# Page05_DDR4L_eMMC.net
KiCad netlist of a schematic drawn in Altium Designer
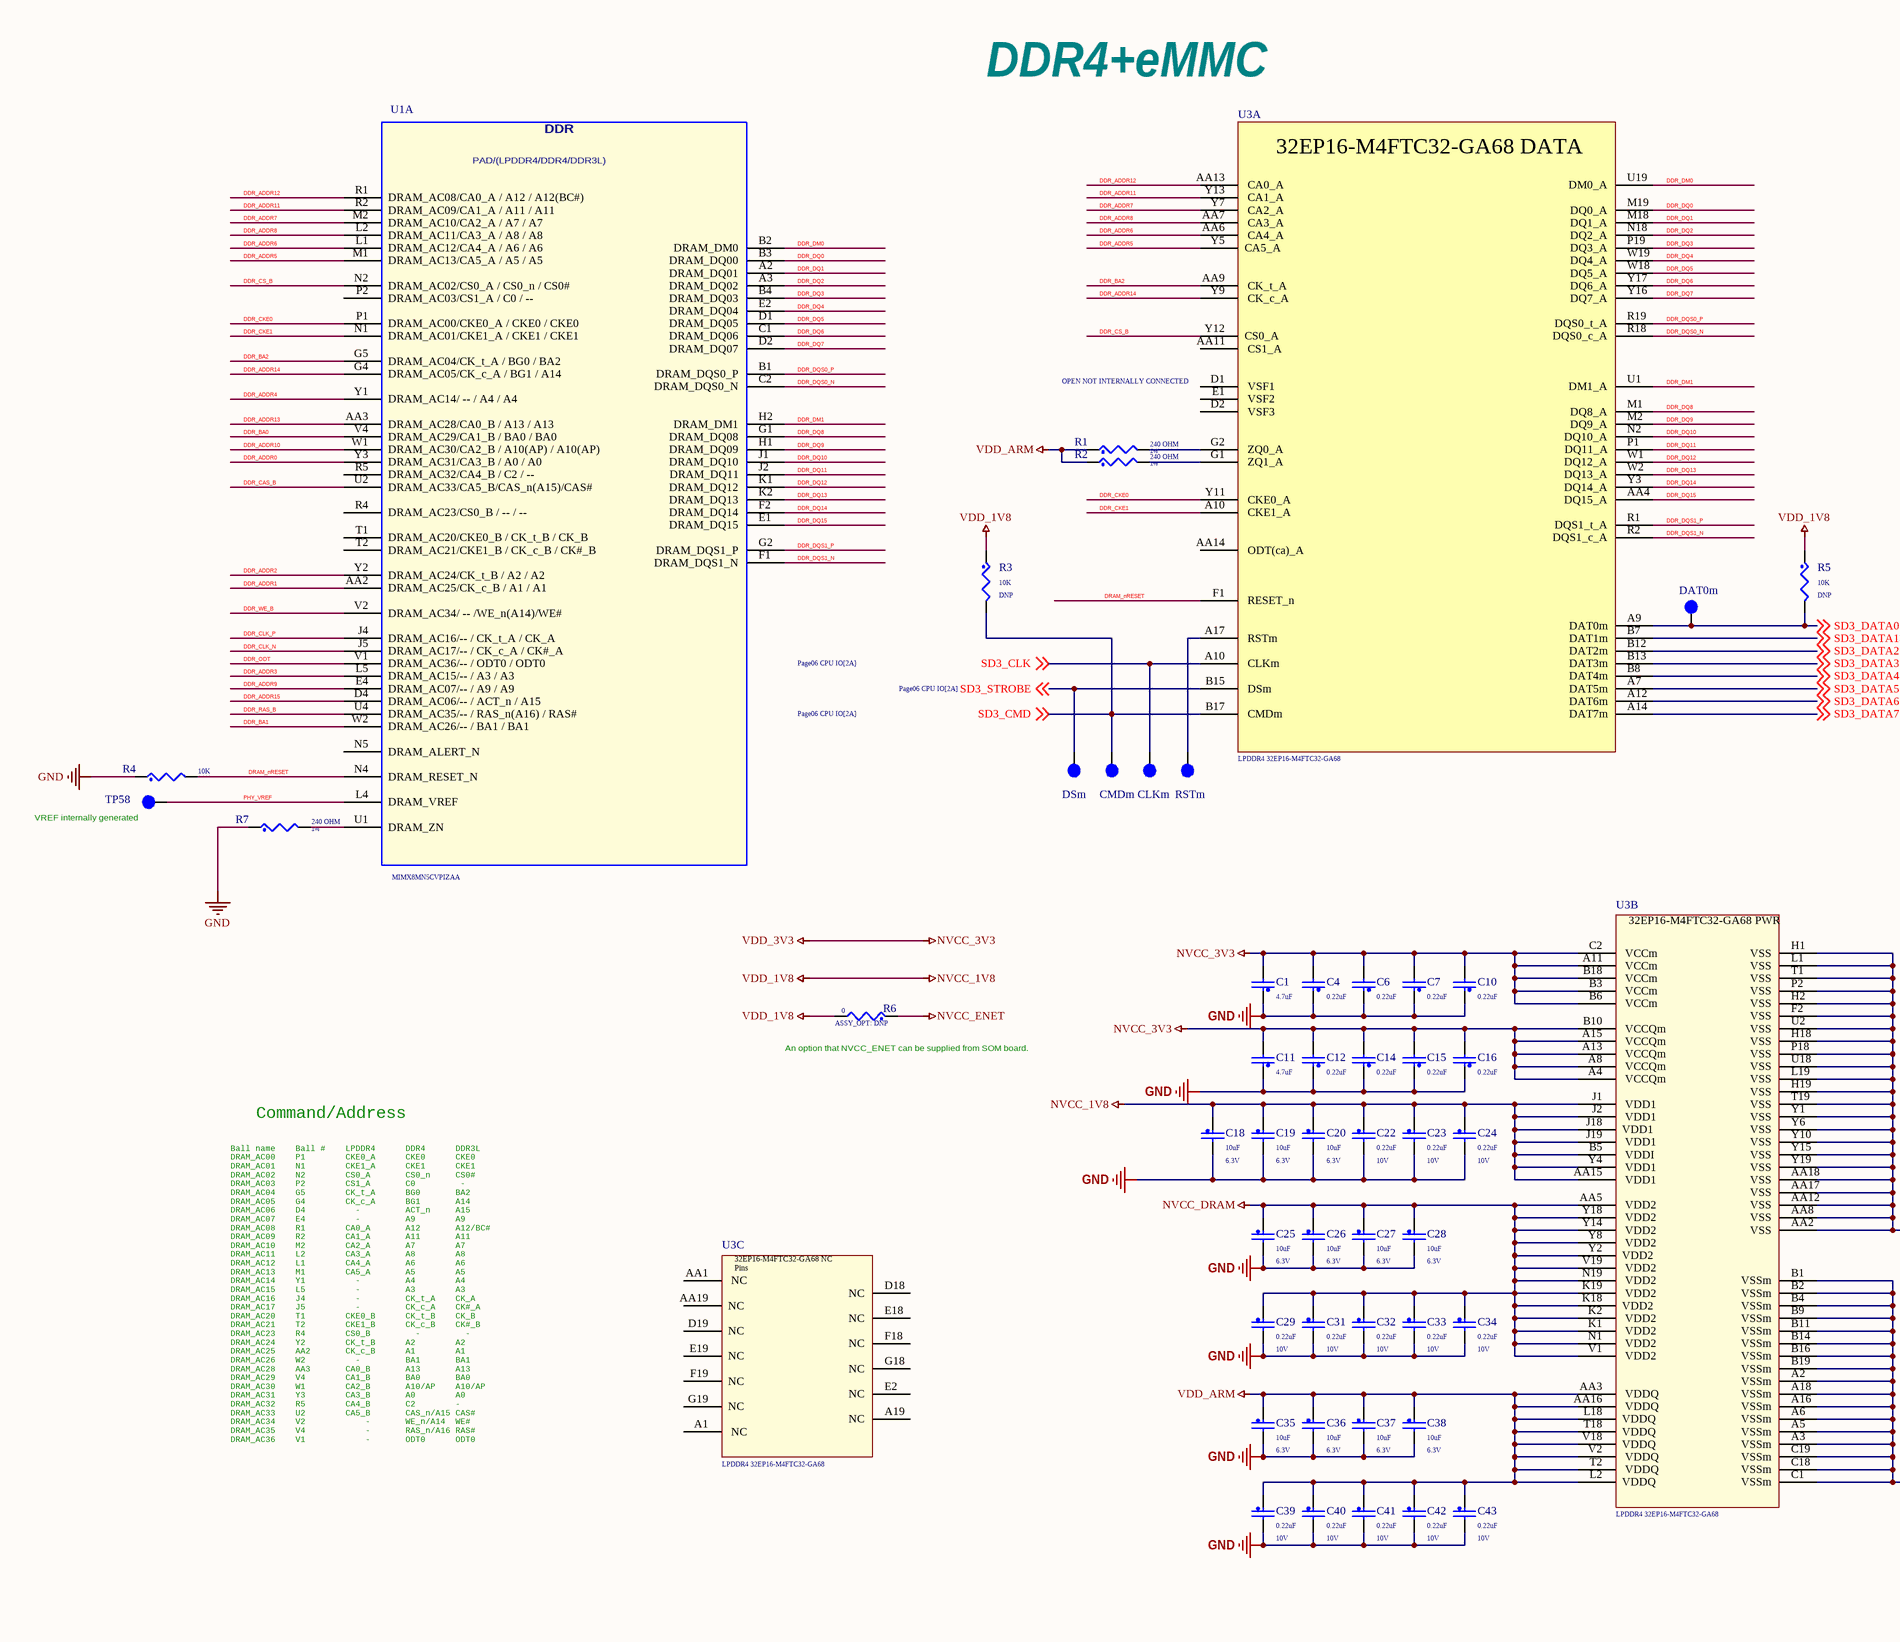
[diagram p0: Page05 DDR4L+eMMC.SchDoc, left]
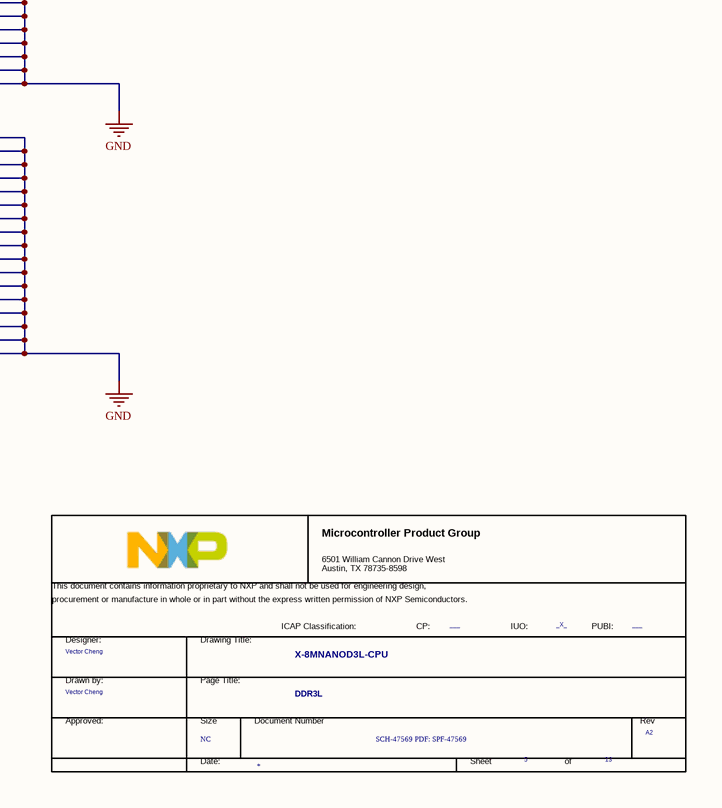
[diagram p1: Page05 DDR4L+eMMC.SchDoc, right]

(export (version "E")
  (design (tool "Eeschema 10.0.6"))
  (components
    (comp (ref "C1") (value "4.7uF") (footprint "0402_CC - C") (libsource (lib "AA_iMX8_M_") (part "CAP_NP")))
    (comp (ref "C4")
      (value "0.22uF")
      (footprint "0201_CC - C")
      (libsource (lib "AA_iMX8_M_") (part "CAP_NP"))
    )
    (comp (ref "C6")
      (value "0.22uF")
      (footprint "0201_CC - C")
      (libsource (lib "AA_iMX8_M_") (part "CAP_NP"))
    )
    (comp (ref "C7")
      (value "0.22uF")
      (footprint "0201_CC - C")
      (libsource (lib "AA_iMX8_M_") (part "CAP_NP"))
    )
    (comp (ref "C10")
      (value "0.22uF")
      (footprint "0201_CC - C")
      (libsource (lib "AA_iMX8_M_") (part "CAP_NP"))
    )
    (comp (ref "C11")
      (value "4.7uF")
      (footprint "0402_CC - C")
      (libsource (lib "AA_iMX8_M_") (part "CAP_NP"))
    )
    (comp (ref "C12")
      (value "0.22uF")
      (footprint "0201_CC - C")
      (libsource (lib "AA_iMX8_M_") (part "CAP_NP"))
    )
    (comp (ref "C14")
      (value "0.22uF")
      (footprint "0201_CC - C")
      (libsource (lib "AA_iMX8_M_") (part "CAP_NP"))
    )
    (comp (ref "C15")
      (value "0.22uF")
      (footprint "0201_CC - C")
      (libsource (lib "AA_iMX8_M_") (part "CAP_NP"))
    )
    (comp (ref "C16")
      (value "0.22uF")
      (footprint "0201_CC - C")
      (libsource (lib "AA_iMX8_M_") (part "CAP_NP"))
    )
    (comp (ref "C18")
      (value "10uF")
      (footprint "0402_CC - C")
      (fields (field (name "VOLTAGE") "6.3V"))
      (libsource (lib "AA_iMX8_M_") (part "CAP_NP"))
    )
    (comp (ref "C19")
      (value "10uF")
      (footprint "0402_CC - C")
      (fields (field (name "VOLTAGE") "6.3V"))
      (libsource (lib "AA_iMX8_M_") (part "CAP_NP"))
    )
    (comp (ref "C20")
      (value "10uF")
      (footprint "0402_CC - C")
      (fields (field (name "VOLTAGE") "6.3V"))
      (libsource (lib "AA_iMX8_M_") (part "CAP_NP"))
    )
    (comp (ref "C22")
      (value "0.22uF")
      (footprint "0201_CC - C")
      (fields (field (name "VOLTAGE") "10V"))
      (libsource (lib "AA_iMX8_M_") (part "CAP_NP"))
    )
    (comp (ref "C23")
      (value "0.22uF")
      (footprint "0201_CC - C")
      (fields (field (name "VOLTAGE") "10V"))
      (libsource (lib "AA_iMX8_M_") (part "CAP_NP"))
    )
    (comp (ref "C24")
      (value "0.22uF")
      (footprint "0201_CC - C")
      (fields (field (name "VOLTAGE") "10V"))
      (libsource (lib "AA_iMX8_M_") (part "CAP_NP"))
    )
    (comp (ref "C25")
      (value "10uF")
      (footprint "0402_CC - C")
      (fields (field (name "VOLTAGE") "6.3V"))
      (libsource (lib "AA_iMX8_M_") (part "CAP_NP"))
    )
    (comp (ref "C26")
      (value "10uF")
      (footprint "0402_CC - C")
      (fields (field (name "VOLTAGE") "6.3V"))
      (libsource (lib "AA_iMX8_M_") (part "CAP_NP"))
    )
    (comp (ref "C27")
      (value "10uF")
      (footprint "0402_CC - C")
      (fields (field (name "VOLTAGE") "6.3V"))
      (libsource (lib "AA_iMX8_M_") (part "CAP_NP"))
    )
    (comp (ref "C28")
      (value "10uF")
      (footprint "0402_CC - C")
      (fields (field (name "VOLTAGE") "6.3V"))
      (libsource (lib "AA_iMX8_M_") (part "CAP_NP"))
    )
    (comp (ref "C29")
      (value "0.22uF")
      (footprint "0201_CC - C")
      (fields (field (name "VOLTAGE") "10V"))
      (libsource (lib "AA_iMX8_M_") (part "CAP_NP"))
    )
    (comp (ref "C31")
      (value "0.22uF")
      (footprint "0201_CC - C")
      (fields (field (name "VOLTAGE") "10V"))
      (libsource (lib "AA_iMX8_M_") (part "CAP_NP"))
    )
    (comp (ref "C32")
      (value "0.22uF")
      (footprint "0201_CC - C")
      (fields (field (name "VOLTAGE") "10V"))
      (libsource (lib "AA_iMX8_M_") (part "CAP_NP"))
    )
    (comp (ref "C33")
      (value "0.22uF")
      (footprint "0201_CC - C")
      (fields (field (name "VOLTAGE") "10V"))
      (libsource (lib "AA_iMX8_M_") (part "CAP_NP"))
    )
    (comp (ref "C34")
      (value "0.22uF")
      (footprint "0201_CC - C")
      (fields (field (name "VOLTAGE") "10V"))
      (libsource (lib "AA_iMX8_M_") (part "CAP_NP"))
    )
    (comp (ref "C35")
      (value "10uF")
      (footprint "0402_CC - C")
      (fields (field (name "VOLTAGE") "6.3V"))
      (libsource (lib "AA_iMX8_M_") (part "CAP_NP"))
    )
    (comp (ref "C36")
      (value "10uF")
      (footprint "0402_CC - C")
      (fields (field (name "VOLTAGE") "6.3V"))
      (libsource (lib "AA_iMX8_M_") (part "CAP_NP"))
    )
    (comp (ref "C37")
      (value "10uF")
      (footprint "0402_CC - C")
      (fields (field (name "VOLTAGE") "6.3V"))
      (libsource (lib "AA_iMX8_M_") (part "CAP_NP"))
    )
    (comp (ref "C38")
      (value "10uF")
      (footprint "0402_CC - C")
      (fields (field (name "VOLTAGE") "6.3V"))
      (libsource (lib "AA_iMX8_M_") (part "CAP_NP"))
    )
    (comp (ref "C39")
      (value "0.22uF")
      (footprint "0201_CC - C")
      (fields (field (name "VOLTAGE") "10V"))
      (libsource (lib "AA_iMX8_M_") (part "CAP_NP"))
    )
    (comp (ref "C40")
      (value "0.22uF")
      (footprint "0201_CC - C")
      (fields (field (name "VOLTAGE") "10V"))
      (libsource (lib "AA_iMX8_M_") (part "CAP_NP"))
    )
    (comp (ref "C41")
      (value "0.22uF")
      (footprint "0201_CC - C")
      (fields (field (name "VOLTAGE") "10V"))
      (libsource (lib "AA_iMX8_M_") (part "CAP_NP"))
    )
    (comp (ref "C42")
      (value "0.22uF")
      (footprint "0201_CC - C")
      (fields (field (name "VOLTAGE") "10V"))
      (libsource (lib "AA_iMX8_M_") (part "CAP_NP"))
    )
    (comp (ref "C43")
      (value "0.22uF")
      (footprint "0201_CC - C")
      (fields (field (name "VOLTAGE") "10V"))
      (libsource (lib "AA_iMX8_M_") (part "CAP_NP"))
    )
    (comp (ref "CLKm")
      (value "tpad_020")
      (footprint "Test Pin")
      (description "TEST POINT PAD 0.5MM DIA SMT, NO PART TO ORDER")
      (libsource (lib "*") (part "TESTLOOP"))
    )
    (comp (ref "CMDm")
      (value "TPAD_015")
      (footprint "Test Pin")
      (description "TEST POINT PAD 15MIL DIA SMT, NO PART TO ORDER")
      (libsource (lib "*") (part "TESTLOOP"))
    )
    (comp (ref "DAT0m")
      (value "tpad_020")
      (footprint "Test Pin")
      (description "TEST POINT PAD 0.5MM DIA SMT, NO PART TO ORDER")
      (libsource (lib "*") (part "TESTLOOP"))
    )
    (comp (ref "DSm")
      (value "TPAD_015")
      (footprint "Test Pin")
      (description "TEST POINT PAD 15MIL DIA SMT, NO PART TO ORDER")
      (libsource (lib "*") (part "TESTLOOP"))
    )
    (comp (ref "R1")
      (value "240 OHM")
      (footprint "0201_RES")
      (description "RES MF 240 OHM 1/20W 1% 0201")
      (fields (field (name "VOLTAGE") "25V") (field (name "TOLERANCE") "1%"))
      (libsource (lib "*") (part "RES"))
    )
    (comp (ref "R2")
      (value "240 OHM")
      (footprint "0201_RES")
      (description "RES MF 240 OHM 1/20W 1% 0201")
      (fields (field (name "VOLTAGE") "25V") (field (name "TOLERANCE") "1%"))
      (libsource (lib "*") (part "RES"))
    )
    (comp (ref "R3")
      (value "10K")
      (footprint "0201_RES")
      (description "RES MF 10K 1/20W 5% 0201")
      (fields (field (name "ASSY_OPT") "DNP") (field (name "TOLERANCE") "5%"))
      (libsource (lib "*") (part "RES"))
    )
    (comp (ref "R4")
      (value "10K")
      (footprint "0201_RES")
      (description "RES MF 10K 1/20W 5% 0201")
      (fields (field (name "TOLERANCE") "5%"))
      (libsource (lib "*") (part "RES"))
    )
    (comp (ref "R5")
      (value "10K")
      (footprint "0201_RES")
      (description "RES MF 10K 1/20W 5% 0201")
      (fields (field (name "ASSY_OPT") "DNP") (field (name "TOLERANCE") "5%"))
      (libsource (lib "*") (part "RES"))
    )
    (comp (ref "R6")
      (value "0")
      (footprint "0402_CC_RES")
      (description "RES MF ZERO OHM 1/16W 5% 0402")
      (fields
        (field (name "ASSY_OPT") "DNP")
        (field (name "TOLERANCE") "5%")
        (field (name "VOLTAGE") "1/16W")
      )
      (libsource (lib "*") (part "RES"))
    )
    (comp (ref "R7")
      (value "240 OHM")
      (footprint "0201_RES")
      (description "RES MF 240 OHM 1/20W 1% 0201")
      (fields (field (name "VOLTAGE") "25V") (field (name "TOLERANCE") "1%"))
      (libsource (lib "*") (part "RES"))
    )
    (comp (ref "RSTm")
      (value "tpad_020")
      (footprint "Test Pin")
      (description "TEST POINT PAD 0.5MM DIA SMT, NO PART TO ORDER")
      (libsource (lib "*") (part "TESTLOOP"))
    )
    (comp (ref "TP58")
      (value "tpad_020")
      (footprint "Test Pin")
      (description "TEST POINT PAD 0.5MM DIA SMT, NO PART TO ORDER")
      (libsource (lib "*") (part "TESTLOOP"))
    )
    (comp (ref "U1")
      (value "MIMX8MN5CVPIZAA")
      (footprint "BGA306C50P21X21_1100X1100X101")
      (description "IC CPU QUAD CORTEX A53+M7 1.4GHZ -- BGA306")
      (libsource (lib "*") (part "MIMX8MN"))
    )
    (comp (ref "U3")
      (value "LPDDR4 32EP16-M4FTC32-GA68")
      (footprint "FBGA144C40P19X21_800X950X80")
      (libsource (lib "") (part "LPDDR4 32EP16-M4FTC32-GA68_1"))
    )
  )
  (nets
    (net (code "1") (name "/DDR_ADDR0") (class "Default")
      (node (ref "U1") (pin "Y3") (pinfunction "DRAM_AC31/CA3_B_/_A0_/_A0_Y3") (pintype "passive"))
    )
    (net (code "2") (name "/DDR_ADDR1") (class "Default")
      (node (ref "U1") (pin "AA2") (pinfunction "DRAM_AC25/CK_c_B_/_A1_/_A1_AA2") (pintype "passive"))
    )
    (net (code "3") (name "/DDR_ADDR2") (class "Default")
      (node (ref "U1") (pin "Y2") (pinfunction "DRAM_AC24/CK_t_B_/_A2_/_A2_Y2") (pintype "passive"))
    )
    (net (code "4") (name "/DDR_ADDR3") (class "Default")
      (node (ref "U1") (pin "L5") (pinfunction "DRAM_AC15/--_/_A3_/_A3_L5") (pintype "passive"))
    )
    (net (code "5") (name "/DDR_ADDR4") (class "Default")
      (node (ref "U1") (pin "Y1") (pinfunction "DRAM_AC14/_--_/_A4_/_A4_Y1") (pintype "passive"))
    )
    (net (code "6") (name "/DDR_ADDR5") (class "Default")
      (node (ref "U1") (pin "M1") (pinfunction "DRAM_AC13/CA5_A_/_A5_/_A5_M1") (pintype "passive"))
      (node (ref "U3") (pin "Y5") (pinfunction "CA5_A_Y5") (pintype "passive"))
    )
    (net (code "7") (name "/DDR_ADDR6") (class "Default")
      (node (ref "U1") (pin "L1") (pinfunction "DRAM_AC12/CA4_A_/_A6_/_A6_L1") (pintype "passive"))
      (node (ref "U3") (pin "AA6") (pinfunction "_CA4_A_AA6") (pintype "passive"))
    )
    (net (code "8") (name "/DDR_ADDR7") (class "Default")
      (node (ref "U1") (pin "M2") (pinfunction "DRAM_AC10/CA2_A_/_A7_/_A7_M2") (pintype "passive"))
      (node (ref "U3") (pin "Y7") (pinfunction "_CA2_A_Y7") (pintype "passive"))
    )
    (net (code "9") (name "/DDR_ADDR8") (class "Default")
      (node (ref "U1") (pin "L2") (pinfunction "DRAM_AC11/CA3_A_/_A8_/_A8_L2") (pintype "passive"))
      (node (ref "U3") (pin "AA7") (pinfunction "_CA3_A_AA7") (pintype "passive"))
    )
    (net (code "10") (name "/DDR_ADDR9") (class "Default")
      (node (ref "U1") (pin "E4") (pinfunction "DRAM_AC07/--_/_A9_/_A9_E4") (pintype "passive"))
    )
    (net (code "11") (name "/DDR_ADDR10") (class "Default")
      (node (ref "U1") (pin "W1") (pinfunction "DRAM_AC30/CA2_B_/_A10(AP)_/_A10(AP)_W1") (pintype "passive"))
    )
    (net (code "12") (name "/DDR_ADDR11") (class "Default")
      (node (ref "U1") (pin "R2") (pinfunction "DRAM_AC09/CA1_A_/_A11_/_A11_R2") (pintype "passive"))
      (node (ref "U3") (pin "Y13") (pinfunction "_CA1_A_Y13") (pintype "passive"))
    )
    (net (code "13") (name "/DDR_ADDR12") (class "Default")
      (node (ref "U1") (pin "R1") (pinfunction "DRAM_AC08/CA0_A_/_A12_/_A12(BC#)_R1") (pintype "passive"))
      (node (ref "U3") (pin "AA13") (pinfunction "_CA0_A_AA13") (pintype "passive"))
    )
    (net (code "14") (name "/DDR_ADDR13") (class "Default")
      (node (ref "U1") (pin "AA3") (pinfunction "DRAM_AC28/CA0_B_/_A13_/_A13_AA3") (pintype "passive"))
    )
    (net (code "15") (name "/DDR_ADDR14") (class "Default")
      (node (ref "U1") (pin "G4") (pinfunction "DRAM_AC05/CK_c_A_/_BG1_/_A14_G4") (pintype "passive"))
      (node (ref "U3") (pin "Y9") (pinfunction "_CK_c_A_Y9") (pintype "passive"))
    )
    (net (code "16") (name "/DDR_ADDR15") (class "Default")
      (node (ref "U1") (pin "D4") (pinfunction "DRAM_AC06/--_/_ACT_n_/_A15_D4") (pintype "passive"))
    )
    (net (code "17") (name "/DDR_BA0") (class "Default")
      (node (ref "U1") (pin "V4") (pinfunction "DRAM_AC29/CA1_B_/_BA0_/_BA0_V4") (pintype "passive"))
    )
    (net (code "18") (name "/DDR_BA1") (class "Default")
      (node (ref "U1") (pin "W2") (pinfunction "DRAM_AC26/--_/_BA1_/_BA1_W2") (pintype "passive"))
    )
    (net (code "19") (name "/DDR_BA2") (class "Default")
      (node (ref "U1") (pin "G5") (pinfunction "DRAM_AC04/CK_t_A_/_BG0_/_BA2_G5") (pintype "passive"))
      (node (ref "U3") (pin "AA9") (pinfunction "_CK_t_A_AA9") (pintype "passive"))
    )
    (net (code "20") (name "/DDR_CAS_B") (class "Default")
      (node (ref "U1") (pin "U2") (pinfunction "DRAM_AC33/CA5_B/CAS_n(A15)/CAS#_U2") (pintype "passive"))
    )
    (net (code "21") (name "/DDR_CKE0") (class "Default")
      (node (ref "U1") (pin "P1") (pinfunction "DRAM_AC00/CKE0_A_/_CKE0_/_CKE0_P1") (pintype "passive"))
      (node (ref "U3") (pin "Y11") (pinfunction "_CKE0_A_Y11") (pintype "passive"))
    )
    (net (code "22") (name "/DDR_CKE1") (class "Default")
      (node (ref "U1") (pin "N1") (pinfunction "DRAM_AC01/CKE1_A_/_CKE1_/_CKE1_N1") (pintype "passive"))
      (node (ref "U3") (pin "A10") (pinfunction "_CKE1_A_A10") (pintype "passive"))
    )
    (net (code "23") (name "/DDR_CLK_N") (class "Default")
      (node (ref "U1") (pin "J5") (pinfunction "DRAM_AC17/--_/_CK_c_A_/_CK#_A_J5") (pintype "passive"))
    )
    (net (code "24") (name "/DDR_CLK_P") (class "Default")
      (node (ref "U1") (pin "J4") (pinfunction "DRAM_AC16/--_/_CK_t_A_/_CK_A_J4") (pintype "passive"))
    )
    (net (code "25") (name "/DDR_CS_B") (class "Default")
      (node (ref "U1") (pin "N2") (pinfunction "DRAM_AC02/CS0_A_/_CS0_n_/_CS0#_N2") (pintype "passive"))
      (node (ref "U3") (pin "Y12") (pinfunction "CS0_A_Y12") (pintype "passive"))
    )
    (net (code "26") (name "/DDR_DM0") (class "Default")
      (node (ref "U1") (pin "B2") (pinfunction "DRAM_DM0_B2") (pintype "passive"))
      (node (ref "U3") (pin "U19") (pinfunction "_DM0_A_U19") (pintype "passive"))
    )
    (net (code "27") (name "/DDR_DM1") (class "Default")
      (node (ref "U1") (pin "H2") (pinfunction "DRAM_DM1_H2") (pintype "passive"))
      (node (ref "U3") (pin "U1") (pinfunction "_DM1_A_U1") (pintype "passive"))
    )
    (net (code "28") (name "/DDR_DQ0") (class "Default")
      (node (ref "U1") (pin "B3") (pinfunction "DRAM_DQ00_B3") (pintype "passive"))
      (node (ref "U3") (pin "M19") (pinfunction "_DQ0_A_M19") (pintype "passive"))
    )
    (net (code "29") (name "/DDR_DQ1") (class "Default")
      (node (ref "U1") (pin "A2") (pinfunction "DRAM_DQ01_A2") (pintype "passive"))
      (node (ref "U3") (pin "M18") (pinfunction "DQ1_A_M18") (pintype "passive"))
    )
    (net (code "30") (name "/DDR_DQ2") (class "Default")
      (node (ref "U1") (pin "A3") (pinfunction "DRAM_DQ02_A3") (pintype "passive"))
      (node (ref "U3") (pin "N18") (pinfunction "DQ2_A_N18") (pintype "passive"))
    )
    (net (code "31") (name "/DDR_DQ3") (class "Default")
      (node (ref "U1") (pin "B4") (pinfunction "DRAM_DQ03_B4") (pintype "passive"))
      (node (ref "U3") (pin "P19") (pinfunction "DQ3_A_P19") (pintype "passive"))
    )
    (net (code "32") (name "/DDR_DQ4") (class "Default")
      (node (ref "U1") (pin "E2") (pinfunction "DRAM_DQ04_E2") (pintype "passive"))
      (node (ref "U3") (pin "W19") (pinfunction "_DQ4_A_W19") (pintype "passive"))
    )
    (net (code "33") (name "/DDR_DQ5") (class "Default")
      (node (ref "U1") (pin "D1") (pinfunction "DRAM_DQ05_D1") (pintype "passive"))
      (node (ref "U3") (pin "W18") (pinfunction "DQ5_A_W18") (pintype "passive"))
    )
    (net (code "34") (name "/DDR_DQ6") (class "Default")
      (node (ref "U1") (pin "C1") (pinfunction "DRAM_DQ06_C1") (pintype "passive"))
      (node (ref "U3") (pin "Y17") (pinfunction "_DQ6_A_Y17") (pintype "passive"))
    )
    (net (code "35") (name "/DDR_DQ7") (class "Default")
      (node (ref "U1") (pin "D2") (pinfunction "DRAM_DQ07_D2") (pintype "passive"))
      (node (ref "U3") (pin "Y16") (pinfunction "_DQ7_A_Y16") (pintype "passive"))
    )
    (net (code "36") (name "/DDR_DQ8") (class "Default")
      (node (ref "U1") (pin "G1") (pinfunction "DRAM_DQ08_G1") (pintype "passive"))
      (node (ref "U3") (pin "M1") (pinfunction "_DQ8_A_M1") (pintype "passive"))
    )
    (net (code "37") (name "/DDR_DQ9") (class "Default")
      (node (ref "U1") (pin "H1") (pinfunction "DRAM_DQ09_H1") (pintype "passive"))
      (node (ref "U3") (pin "M2") (pinfunction "_DQ9_A_M2") (pintype "passive"))
    )
    (net (code "38") (name "/DDR_DQ10") (class "Default")
      (node (ref "U1") (pin "J1") (pinfunction "DRAM_DQ10_J1") (pintype "passive"))
      (node (ref "U3") (pin "N2") (pinfunction "_DQ10_A_N2") (pintype "passive"))
    )
    (net (code "39") (name "/DDR_DQ11") (class "Default")
      (node (ref "U1") (pin "J2") (pinfunction "DRAM_DQ11_J2") (pintype "passive"))
      (node (ref "U3") (pin "P1") (pinfunction "_DQ11_A_P1") (pintype "passive"))
    )
    (net (code "40") (name "/DDR_DQ12") (class "Default")
      (node (ref "U1") (pin "K1") (pinfunction "DRAM_DQ12_K1") (pintype "passive"))
      (node (ref "U3") (pin "W1") (pinfunction "_DQ12_A_W1") (pintype "passive"))
    )
    (net (code "41") (name "/DDR_DQ13") (class "Default")
      (node (ref "U1") (pin "K2") (pinfunction "DRAM_DQ13_K2") (pintype "passive"))
      (node (ref "U3") (pin "W2") (pinfunction "_DQ13_A_W2") (pintype "passive"))
    )
    (net (code "42") (name "/DDR_DQ14") (class "Default")
      (node (ref "U1") (pin "F2") (pinfunction "DRAM_DQ14_F2") (pintype "passive"))
      (node (ref "U3") (pin "Y3") (pinfunction "_DQ14_A_Y3") (pintype "passive"))
    )
    (net (code "43") (name "/DDR_DQ15") (class "Default")
      (node (ref "U1") (pin "E1") (pinfunction "DRAM_DQ15_E1") (pintype "passive"))
      (node (ref "U3") (pin "AA4") (pinfunction "_DQ15_A_AA4") (pintype "passive"))
    )
    (net (code "44") (name "/DDR_DQS0_N") (class "Default")
      (node (ref "U1") (pin "C2") (pinfunction "DRAM_DQS0_N_C2") (pintype "passive"))
      (node (ref "U3") (pin "R18") (pinfunction "DQS0_c_A_R18") (pintype "passive"))
    )
    (net (code "45") (name "/DDR_DQS0_P") (class "Default")
      (node (ref "U1") (pin "B1") (pinfunction "DRAM_DQS0_P_B1") (pintype "passive"))
      (node (ref "U3") (pin "R19") (pinfunction "_DQS0_t_A_R19") (pintype "passive"))
    )
    (net (code "46") (name "/DDR_DQS1_N") (class "Default")
      (node (ref "U1") (pin "F1") (pinfunction "DRAM_DQS1_N_F1") (pintype "passive"))
      (node (ref "U3") (pin "R2") (pinfunction "_DQS1_c_A_R2") (pintype "passive"))
    )
    (net (code "47") (name "/DDR_DQS1_P") (class "Default")
      (node (ref "U1") (pin "G2") (pinfunction "DRAM_DQS1_P_G2") (pintype "passive"))
      (node (ref "U3") (pin "R1") (pinfunction "_DQS1_t_A_R1") (pintype "passive"))
    )
    (net (code "48") (name "/DDR_ODT") (class "Default")
      (node (ref "U1") (pin "V1") (pinfunction "DRAM_AC36/--_/_ODT0_/_ODT0_V1") (pintype "passive"))
    )
    (net (code "49") (name "/DDR_RAS_B") (class "Default")
      (node (ref "U1") (pin "U4") (pinfunction "DRAM_AC35/--_/_RAS_n(A16)_/_RAS#_U4") (pintype "passive"))
    )
    (net (code "50") (name "/DDR_WE_B") (class "Default")
      (node (ref "U1") (pin "V2") (pinfunction "DRAM_AC34/_--_/WE_n(A14)/WE#_V2") (pintype "passive"))
    )
    (net (code "51") (name "/DRAM_nRESET") (class "Default")
      (node (ref "R4") (pin "2") (pinfunction "2_2") (pintype "passive"))
      (node (ref "U1") (pin "N4") (pinfunction "DRAM_RESET_N_N4") (pintype "passive"))
      (node (ref "U3") (pin "F1") (pinfunction "_RESET_n_F1") (pintype "passive"))
    )
    (net (code "52") (name "/PHY_VREF") (class "Default")
      (node (ref "TP58") (pin "1") (pinfunction "Pin1_1") (pintype "passive"))
      (node (ref "U1") (pin "L4") (pinfunction "DRAM_VREF_L4") (pintype "passive"))
    )
    (net (code "53") (name "GND") (class "Default")
      (node (ref "C1") (pin "1") (pinfunction "1_1") (pintype "passive"))
      (node (ref "C10") (pin "1") (pinfunction "1_1") (pintype "passive"))
      (node (ref "C11") (pin "1") (pinfunction "1_1") (pintype "passive"))
      (node (ref "C12") (pin "1") (pinfunction "1_1") (pintype "passive"))
      (node (ref "C14") (pin "1") (pinfunction "1_1") (pintype "passive"))
      (node (ref "C15") (pin "1") (pinfunction "1_1") (pintype "passive"))
      (node (ref "C16") (pin "1") (pinfunction "1_1") (pintype "passive"))
      (node (ref "C18") (pin "2") (pinfunction "2_2") (pintype "passive"))
      (node (ref "C19") (pin "2") (pinfunction "2_2") (pintype "passive"))
      (node (ref "C20") (pin "2") (pinfunction "2_2") (pintype "passive"))
      (node (ref "C22") (pin "2") (pinfunction "2_2") (pintype "passive"))
      (node (ref "C23") (pin "2") (pinfunction "2_2") (pintype "passive"))
      (node (ref "C24") (pin "2") (pinfunction "2_2") (pintype "passive"))
      (node (ref "C25") (pin "2") (pinfunction "2_2") (pintype "passive"))
      (node (ref "C26") (pin "2") (pinfunction "2_2") (pintype "passive"))
      (node (ref "C27") (pin "2") (pinfunction "2_2") (pintype "passive"))
      (node (ref "C28") (pin "2") (pinfunction "2_2") (pintype "passive"))
      (node (ref "C29") (pin "2") (pinfunction "2_2") (pintype "passive"))
      (node (ref "C31") (pin "2") (pinfunction "2_2") (pintype "passive"))
      (node (ref "C32") (pin "2") (pinfunction "2_2") (pintype "passive"))
      (node (ref "C33") (pin "2") (pinfunction "2_2") (pintype "passive"))
      (node (ref "C34") (pin "2") (pinfunction "2_2") (pintype "passive"))
      (node (ref "C35") (pin "2") (pinfunction "2_2") (pintype "passive"))
      (node (ref "C36") (pin "2") (pinfunction "2_2") (pintype "passive"))
      (node (ref "C37") (pin "2") (pinfunction "2_2") (pintype "passive"))
      (node (ref "C38") (pin "2") (pinfunction "2_2") (pintype "passive"))
      (node (ref "C39") (pin "2") (pinfunction "2_2") (pintype "passive"))
      (node (ref "C4") (pin "1") (pinfunction "1_1") (pintype "passive"))
      (node (ref "C40") (pin "2") (pinfunction "2_2") (pintype "passive"))
      (node (ref "C41") (pin "2") (pinfunction "2_2") (pintype "passive"))
      (node (ref "C42") (pin "2") (pinfunction "2_2") (pintype "passive"))
      (node (ref "C43") (pin "2") (pinfunction "2_2") (pintype "passive"))
      (node (ref "C6") (pin "1") (pinfunction "1_1") (pintype "passive"))
      (node (ref "C7") (pin "1") (pinfunction "1_1") (pintype "passive"))
      (node (ref "R4") (pin "1") (pinfunction "1_1") (pintype "passive"))
      (node (ref "R7") (pin "1") (pinfunction "1_1") (pintype "passive"))
      (node (ref "U3") (pin "A16") (pinfunction "_VSSm_A16") (pintype "power_in"))
      (node (ref "U3") (pin "A18") (pinfunction "_VSSm_A18") (pintype "power_in"))
      (node (ref "U3") (pin "A2") (pinfunction "_VSSm_A2") (pintype "power_in"))
      (node (ref "U3") (pin "A3") (pinfunction "VSSm_A3") (pintype "power_in"))
      (node (ref "U3") (pin "A5") (pinfunction "_VSSm_A5") (pintype "power_in"))
      (node (ref "U3") (pin "A6") (pinfunction "_VSSm_A6") (pintype "power_in"))
      (node (ref "U3") (pin "AA12") (pinfunction "_VSS_AA12") (pintype "power_in"))
      (node (ref "U3") (pin "AA17") (pinfunction "_VSS_AA17") (pintype "power_in"))
      (node (ref "U3") (pin "AA18") (pinfunction "VSS_AA18") (pintype "power_in"))
      (node (ref "U3") (pin "AA2") (pinfunction "VSS_AA2") (pintype "power_in"))
      (node (ref "U3") (pin "AA8") (pinfunction "_VSS_AA8") (pintype "power_in"))
      (node (ref "U3") (pin "B1") (pinfunction "_VSSm_B1") (pintype "power_in"))
      (node (ref "U3") (pin "B11") (pinfunction "_VSSm_B11") (pintype "power_in"))
      (node (ref "U3") (pin "B14") (pinfunction "_VSSm_B14") (pintype "power_in"))
      (node (ref "U3") (pin "B16") (pinfunction "_VSSm_B16") (pintype "power_in"))
      (node (ref "U3") (pin "B19") (pinfunction "_VSSm_B19") (pintype "power_in"))
      (node (ref "U3") (pin "B2") (pinfunction "_VSSm_B2") (pintype "power_in"))
      (node (ref "U3") (pin "B4") (pinfunction "_VSSm_B4") (pintype "power_in"))
      (node (ref "U3") (pin "B9") (pinfunction "_VSSm_B9") (pintype "power_in"))
      (node (ref "U3") (pin "C1") (pinfunction "_VSSm_C1") (pintype "power_in"))
      (node (ref "U3") (pin "C18") (pinfunction "VSSm_C18") (pintype "power_in"))
      (node (ref "U3") (pin "C19") (pinfunction "_VSSm_C19") (pintype "power_in"))
      (node (ref "U3") (pin "F2") (pinfunction "_VSS_F2") (pintype "power_in"))
      (node (ref "U3") (pin "H1") (pinfunction "_VSS_H1") (pintype "power_in"))
      (node (ref "U3") (pin "H18") (pinfunction "VSS_H18") (pintype "power_in"))
      (node (ref "U3") (pin "H19") (pinfunction "VSS_H19") (pintype "power_in"))
      (node (ref "U3") (pin "H2") (pinfunction "VSS_H2") (pintype "power_in"))
      (node (ref "U3") (pin "L1") (pinfunction "_VSS_L1") (pintype "power_in"))
      (node (ref "U3") (pin "L19") (pinfunction "VSS_L19") (pintype "power_in"))
      (node (ref "U3") (pin "P18") (pinfunction "VSS_P18") (pintype "power_in"))
      (node (ref "U3") (pin "P2") (pinfunction "_VSS_P2") (pintype "power_in"))
      (node (ref "U3") (pin "T1") (pinfunction "_VSS_T1") (pintype "power_in"))
      (node (ref "U3") (pin "T19") (pinfunction "VSS_T19") (pintype "power_in"))
      (node (ref "U3") (pin "U18") (pinfunction "VSS_U18") (pintype "power_in"))
      (node (ref "U3") (pin "U2") (pinfunction "_VSS_U2") (pintype "power_in"))
      (node (ref "U3") (pin "Y1") (pinfunction "_VSS_Y1") (pintype "power_in"))
      (node (ref "U3") (pin "Y10") (pinfunction "_VSS_Y10") (pintype "power_in"))
      (node (ref "U3") (pin "Y15") (pinfunction "_VSS_Y15") (pintype "power_in"))
      (node (ref "U3") (pin "Y19") (pinfunction "VSS_Y19") (pintype "power_in"))
      (node (ref "U3") (pin "Y6") (pinfunction "_VSS_Y6") (pintype "power_in"))
    )
    (net (code "54") (name "NVCC_1V8") (class "Default")
      (node (ref "C18") (pin "1") (pinfunction "1_1") (pintype "passive"))
      (node (ref "C19") (pin "1") (pinfunction "1_1") (pintype "passive"))
      (node (ref "C20") (pin "1") (pinfunction "1_1") (pintype "passive"))
      (node (ref "C22") (pin "1") (pinfunction "1_1") (pintype "passive"))
      (node (ref "C23") (pin "1") (pinfunction "1_1") (pintype "passive"))
      (node (ref "C24") (pin "1") (pinfunction "1_1") (pintype "passive"))
      (node (ref "R3") (pin "1") (pinfunction "1_1") (pintype "passive"))
      (node (ref "R5") (pin "1") (pinfunction "1_1") (pintype "passive"))
      (node (ref "R6") (pin "2") (pinfunction "2_2") (pintype "passive"))
      (node (ref "U3") (pin "AA15") (pinfunction "_VDD1_AA15") (pintype "power_in"))
      (node (ref "U3") (pin "B5") (pinfunction "_VDDI_B5") (pintype "power_in"))
      (node (ref "U3") (pin "J1") (pinfunction "_VDD1_J1") (pintype "power_in"))
      (node (ref "U3") (pin "J18") (pinfunction "VDD1_J18") (pintype "power_in"))
      (node (ref "U3") (pin "J19") (pinfunction "_VDD1_J19") (pintype "power_in"))
      (node (ref "U3") (pin "J2") (pinfunction "_VDD1_J2") (pintype "power_in"))
      (node (ref "U3") (pin "Y4") (pinfunction "_VDD1_Y4") (pintype "power_in"))
    )
    (net (code "55") (name "NVCC_3V3") (class "Default")
      (node (ref "C1") (pin "2") (pinfunction "2_2") (pintype "passive"))
      (node (ref "C10") (pin "2") (pinfunction "2_2") (pintype "passive"))
      (node (ref "C11") (pin "2") (pinfunction "2_2") (pintype "passive"))
      (node (ref "C12") (pin "2") (pinfunction "2_2") (pintype "passive"))
      (node (ref "C14") (pin "2") (pinfunction "2_2") (pintype "passive"))
      (node (ref "C15") (pin "2") (pinfunction "2_2") (pintype "passive"))
      (node (ref "C16") (pin "2") (pinfunction "2_2") (pintype "passive"))
      (node (ref "C4") (pin "2") (pinfunction "2_2") (pintype "passive"))
      (node (ref "C6") (pin "2") (pinfunction "2_2") (pintype "passive"))
      (node (ref "C7") (pin "2") (pinfunction "2_2") (pintype "passive"))
      (node (ref "U3") (pin "A11") (pinfunction "_VCCm_A11") (pintype "power_in"))
      (node (ref "U3") (pin "A13") (pinfunction "_VCCQm_A13") (pintype "power_in"))
      (node (ref "U3") (pin "A15") (pinfunction "_VCCQm_A15") (pintype "power_in"))
      (node (ref "U3") (pin "A4") (pinfunction "_VCCQm_A4") (pintype "power_in"))
      (node (ref "U3") (pin "A8") (pinfunction "_VCCQm_A8") (pintype "power_in"))
      (node (ref "U3") (pin "B10") (pinfunction "_VCCQm_B10") (pintype "power_in"))
      (node (ref "U3") (pin "B18") (pinfunction "_VCCm_B18") (pintype "power_in"))
      (node (ref "U3") (pin "B3") (pinfunction "_VCCm_B3") (pintype "power_in"))
      (node (ref "U3") (pin "B6") (pinfunction "_VCCm_B6") (pintype "power_in"))
      (node (ref "U3") (pin "C2") (pinfunction "_VCCm_C2") (pintype "power_in"))
    )
    (net (code "56") (name "NVCC_DRAM") (class "Default")
      (node (ref "C25") (pin "1") (pinfunction "1_1") (pintype "passive"))
      (node (ref "C26") (pin "1") (pinfunction "1_1") (pintype "passive"))
      (node (ref "C27") (pin "1") (pinfunction "1_1") (pintype "passive"))
      (node (ref "C28") (pin "1") (pinfunction "1_1") (pintype "passive"))
      (node (ref "C29") (pin "1") (pinfunction "1_1") (pintype "passive"))
      (node (ref "C31") (pin "1") (pinfunction "1_1") (pintype "passive"))
      (node (ref "C32") (pin "1") (pinfunction "1_1") (pintype "passive"))
      (node (ref "C33") (pin "1") (pinfunction "1_1") (pintype "passive"))
      (node (ref "C34") (pin "1") (pinfunction "1_1") (pintype "passive"))
      (node (ref "U3") (pin "AA5") (pinfunction "_VDD2_AA5") (pintype "power_in"))
      (node (ref "U3") (pin "K1") (pinfunction "_VDD2_K1") (pintype "power_in"))
      (node (ref "U3") (pin "K18") (pinfunction "VDD2_K18") (pintype "power_in"))
      (node (ref "U3") (pin "K19") (pinfunction "_VDD2_K19") (pintype "power_in"))
      (node (ref "U3") (pin "K2") (pinfunction "_VDD2_K2") (pintype "power_in"))
      (node (ref "U3") (pin "N1") (pinfunction "_VDD2_N1") (pintype "power_in"))
      (node (ref "U3") (pin "N19") (pinfunction "_VDD2_N19") (pintype "power_in"))
      (node (ref "U3") (pin "V1") (pinfunction "_VDD2_V1") (pintype "power_in"))
      (node (ref "U3") (pin "V19") (pinfunction "_VDD2_V19") (pintype "power_in"))
      (node (ref "U3") (pin "Y14") (pinfunction "_VDD2_Y14") (pintype "power_in"))
      (node (ref "U3") (pin "Y18") (pinfunction "_VDD2_Y18") (pintype "power_in"))
      (node (ref "U3") (pin "Y2") (pinfunction "VDD2_Y2") (pintype "power_in"))
      (node (ref "U3") (pin "Y8") (pinfunction "_VDD2_Y8") (pintype "power_in"))
    )
    (net (code "57") (name "NVCC_ENET") (class "Default")
      (node (ref "R6") (pin "1") (pinfunction "1_1") (pintype "passive"))
    )
    (net (code "58") (name "Net-(RSTm-Pin1)") (class "Default")
      (node (ref "RSTm") (pin "1") (pinfunction "Pin1_1") (pintype "passive"))
      (node (ref "U3") (pin "A17") (pinfunction "_RSTm_A17") (pintype "passive"))
    )
    (net (code "59") (name "Net-(U1A-DRAM_ZN)") (class "Default")
      (node (ref "R7") (pin "2") (pinfunction "2_2") (pintype "passive"))
      (node (ref "U1") (pin "U1") (pinfunction "DRAM_ZN_U1") (pintype "passive"))
    )
    (net (code "60") (name "Net-(U3A-_ZQ0_A)") (class "Default")
      (node (ref "R1") (pin "2") (pinfunction "2_2") (pintype "passive"))
      (node (ref "U3") (pin "G2") (pinfunction "_ZQ0_A_G2") (pintype "passive"))
    )
    (net (code "61") (name "Net-(U3A-_ZQ1_A)") (class "Default")
      (node (ref "R2") (pin "2") (pinfunction "2_2") (pintype "passive"))
      (node (ref "U3") (pin "G1") (pinfunction "_ZQ1_A_G1") (pintype "passive"))
    )
    (net (code "62") (name "SD3_CLK") (class "Default")
      (node (ref "CLKm") (pin "1") (pinfunction "Pin1_1") (pintype "passive"))
      (node (ref "U3") (pin "A10") (pinfunction "_CLKm_A10") (pintype "passive"))
    )
    (net (code "63") (name "SD3_CMD") (class "Default")
      (node (ref "CMDm") (pin "1") (pinfunction "Pin1_1") (pintype "passive"))
      (node (ref "R3") (pin "2") (pinfunction "2_2") (pintype "passive"))
      (node (ref "U3") (pin "B17") (pinfunction "_CMDm_B17") (pintype "passive"))
    )
    (net (code "64") (name "SD3_DATA0") (class "Default")
      (node (ref "DAT0m") (pin "1") (pinfunction "Pin1_1") (pintype "passive"))
      (node (ref "R5") (pin "2") (pinfunction "2_2") (pintype "passive"))
      (node (ref "U3") (pin "A9") (pinfunction "_DAT0m_A9") (pintype "passive"))
    )
    (net (code "65") (name "SD3_DATA1") (class "Default")
      (node (ref "U3") (pin "B7") (pinfunction "DAT1m_B7") (pintype "passive"))
    )
    (net (code "66") (name "SD3_DATA2") (class "Default")
      (node (ref "U3") (pin "B12") (pinfunction "_DAT2m_B12") (pintype "passive"))
    )
    (net (code "67") (name "SD3_DATA3") (class "Default")
      (node (ref "U3") (pin "B13") (pinfunction "_DAT3m_B13") (pintype "passive"))
    )
    (net (code "68") (name "SD3_DATA4") (class "Default")
      (node (ref "U3") (pin "B8") (pinfunction "_DAT4m_B8") (pintype "passive"))
    )
    (net (code "69") (name "SD3_DATA5") (class "Default")
      (node (ref "U3") (pin "A7") (pinfunction "_DAT5m_A7") (pintype "passive"))
    )
    (net (code "70") (name "SD3_DATA6") (class "Default")
      (node (ref "U3") (pin "A12") (pinfunction "_DAT6m_A12") (pintype "passive"))
    )
    (net (code "71") (name "SD3_DATA7") (class "Default")
      (node (ref "U3") (pin "A14") (pinfunction "_DAT7m_A14") (pintype "passive"))
    )
    (net (code "72") (name "SD3_STROBE") (class "Default")
      (node (ref "DSm") (pin "1") (pinfunction "Pin1_1") (pintype "passive"))
      (node (ref "U3") (pin "B15") (pinfunction "_DSm_B15") (pintype "passive"))
    )
    (net (code "73") (name "VDD_ARM") (class "Default")
      (node (ref "C35") (pin "1") (pinfunction "1_1") (pintype "passive"))
      (node (ref "C36") (pin "1") (pinfunction "1_1") (pintype "passive"))
      (node (ref "C37") (pin "1") (pinfunction "1_1") (pintype "passive"))
      (node (ref "C38") (pin "1") (pinfunction "1_1") (pintype "passive"))
      (node (ref "C39") (pin "1") (pinfunction "1_1") (pintype "passive"))
      (node (ref "C40") (pin "1") (pinfunction "1_1") (pintype "passive"))
      (node (ref "C41") (pin "1") (pinfunction "1_1") (pintype "passive"))
      (node (ref "C42") (pin "1") (pinfunction "1_1") (pintype "passive"))
      (node (ref "C43") (pin "1") (pinfunction "1_1") (pintype "passive"))
      (node (ref "R1") (pin "1") (pinfunction "1_1") (pintype "passive"))
      (node (ref "R2") (pin "1") (pinfunction "1_1") (pintype "passive"))
      (node (ref "U3") (pin "AA16") (pinfunction "_VDDQ_AA16") (pintype "power_in"))
      (node (ref "U3") (pin "AA3") (pinfunction "_VDDQ_AA3") (pintype "power_in"))
      (node (ref "U3") (pin "L18") (pinfunction "VDDQ_L18") (pintype "power_in"))
      (node (ref "U3") (pin "L2") (pinfunction "VDDQ_L2") (pintype "power_in"))
      (node (ref "U3") (pin "T18") (pinfunction "VDDQ_T18") (pintype "power_in"))
      (node (ref "U3") (pin "T2") (pinfunction "_VDDQ_T2") (pintype "power_in"))
      (node (ref "U3") (pin "V18") (pinfunction "VDDQ_V18") (pintype "power_in"))
      (node (ref "U3") (pin "V2") (pinfunction "_VDDQ_V2") (pintype "power_in"))
    )
    (net (code "74") (name "unconnected-(U1A-DRAM_AC03{slash}CS1_A_{slash}_C0_{slash}_---PadP2)") (class "Default")
      (node (ref "U1") (pin "P2") (pinfunction "DRAM_AC03/CS1_A_/_C0_/_--_P2") (pintype "passive"))
    )
    (net (code "75") (name "unconnected-(U1A-DRAM_AC20{slash}CKE0_B_{slash}_CK_t_B_{slash}_CK_B-PadT1)") (class "Default")
      (node (ref "U1") (pin "T1") (pinfunction "DRAM_AC20/CKE0_B_/_CK_t_B_/_CK_B_T1") (pintype "passive"))
    )
    (net (code "76") (name "unconnected-(U1A-DRAM_AC21{slash}CKE1_B_{slash}_CK_c_B_{slash}_CK#_B-PadT2)") (class "Default")
      (node (ref "U1") (pin "T2") (pinfunction "DRAM_AC21/CKE1_B_/_CK_c_B_/_CK#_B_T2") (pintype "passive"))
    )
    (net (code "77") (name "unconnected-(U1A-DRAM_AC23{slash}CS0_B_{slash}_--_{slash}_---PadR4)") (class "Default")
      (node (ref "U1") (pin "R4") (pinfunction "DRAM_AC23/CS0_B_/_--_/_--_R4") (pintype "passive"))
    )
    (net (code "78") (name "unconnected-(U1A-DRAM_AC32{slash}CA4_B_{slash}_C2_{slash}_---PadR5)") (class "Default")
      (node (ref "U1") (pin "R5") (pinfunction "DRAM_AC32/CA4_B_/_C2_/_--_R5") (pintype "passive"))
    )
    (net (code "79") (name "unconnected-(U1A-DRAM_ALERT_N-PadN5)") (class "Default")
      (node (ref "U1") (pin "N5") (pinfunction "DRAM_ALERT_N_N5") (pintype "passive"))
    )
    (net (code "80") (name "unconnected-(U3A-_CS1_A-PadAA11)") (class "Default")
      (node (ref "U3") (pin "AA11") (pinfunction "_CS1_A_AA11") (pintype "passive"))
    )
    (net (code "81") (name "unconnected-(U3A-_ODT(ca)_A-PadAA14)") (class "Default")
      (node (ref "U3") (pin "AA14") (pinfunction "_ODT(ca)_A_AA14") (pintype "passive"))
    )
    (net (code "82") (name "unconnected-(U3A-_VSF1-PadD1)") (class "Default")
      (node (ref "U3") (pin "D1") (pinfunction "_VSF1_D1") (pintype "passive"))
    )
    (net (code "83") (name "unconnected-(U3A-_VSF2-PadE1)") (class "Default")
      (node (ref "U3") (pin "E1") (pinfunction "_VSF2_E1") (pintype "passive"))
    )
    (net (code "84") (name "unconnected-(U3A-_VSF3-PadD2)") (class "Default")
      (node (ref "U3") (pin "D2") (pinfunction "_VSF3_D2") (pintype "passive"))
    )
    (net (code "85") (name "unconnected-(U3C-NC-PadA19)") (class "Default")
      (node (ref "U3") (pin "A19") (pinfunction "NC_A19") (pintype "passive"))
    )
    (net (code "86") (name "unconnected-(U3C-NC-PadAA19)") (class "Default")
      (node (ref "U3") (pin "AA19") (pinfunction "NC_AA19") (pintype "passive"))
    )
    (net (code "87") (name "unconnected-(U3C-NC-PadD18)") (class "Default")
      (node (ref "U3") (pin "D18") (pinfunction "NC_D18") (pintype "passive"))
    )
    (net (code "88") (name "unconnected-(U3C-NC-PadD19)") (class "Default")
      (node (ref "U3") (pin "D19") (pinfunction "NC_D19") (pintype "passive"))
    )
    (net (code "89") (name "unconnected-(U3C-NC-PadE2)") (class "Default")
      (node (ref "U3") (pin "E2") (pinfunction "NC_E2") (pintype "passive"))
    )
    (net (code "90") (name "unconnected-(U3C-NC-PadE18)") (class "Default")
      (node (ref "U3") (pin "E18") (pinfunction "NC_E18") (pintype "passive"))
    )
    (net (code "91") (name "unconnected-(U3C-NC-PadE19)") (class "Default")
      (node (ref "U3") (pin "E19") (pinfunction "NC_E19") (pintype "passive"))
    )
    (net (code "92") (name "unconnected-(U3C-NC-PadF18)") (class "Default")
      (node (ref "U3") (pin "F18") (pinfunction "NC_F18") (pintype "passive"))
    )
    (net (code "93") (name "unconnected-(U3C-NC-PadF19)") (class "Default")
      (node (ref "U3") (pin "F19") (pinfunction "NC_F19") (pintype "passive"))
    )
    (net (code "94") (name "unconnected-(U3C-NC-PadG18)") (class "Default")
      (node (ref "U3") (pin "G18") (pinfunction "NC_G18") (pintype "passive"))
    )
    (net (code "95") (name "unconnected-(U3C-NC-PadG19)") (class "Default")
      (node (ref "U3") (pin "G19") (pinfunction "NC_G19") (pintype "passive"))
    )
    (net (code "96") (name "unconnected-(U3C-_NC-PadA1)") (class "Default")
      (node (ref "U3") (pin "A1") (pinfunction "_NC_A1") (pintype "passive"))
    )
    (net (code "97") (name "unconnected-(U3C-_NC-PadAA1)") (class "Default")
      (node (ref "U3") (pin "AA1") (pinfunction "_NC_AA1") (pintype "passive"))
    )
  )
)
